# esp32_LoRa.net
KiCad netlist of a schematic drawn in EAGLE
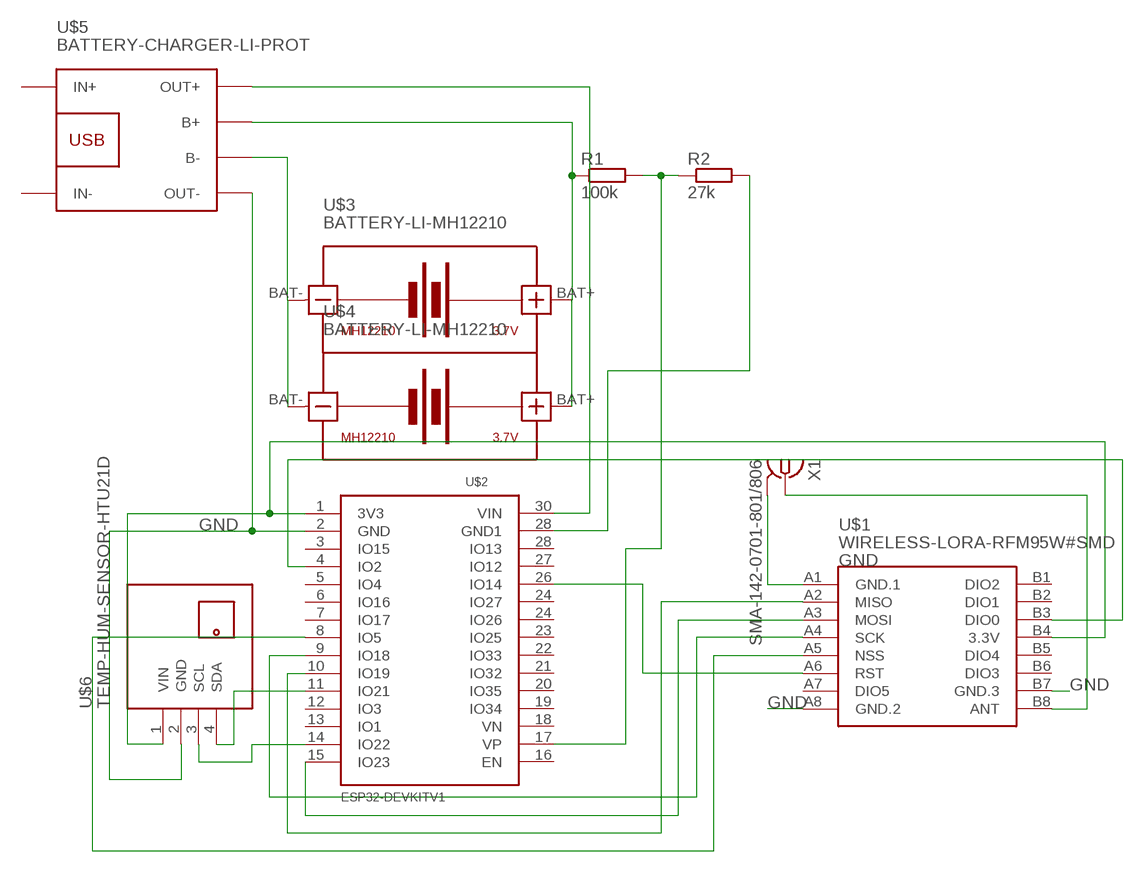
[diagram p0: schematic, sheet 1]

(export (version "E")
  (design (tool "Eeschema 10.0.6"))
  (components
    (comp (ref "R1")
      (value "100k")
      (footprint "eagle-import:0204_7")
      (libsource (lib "eagle-import") (part "R-EU_0204/7"))
    )
    (comp (ref "R2")
      (value "27k")
      (footprint "eagle-import:0204_7")
      (libsource (lib "eagle-import") (part "R-EU_0204/7"))
    )
    (comp (ref "U$1")
      (value "WIRELESS-LORA-RFM95W#SMD")
      (footprint "eagle-import:WIRELESS-LORA-RFM95W#SMD")
      (libsource (lib "eagle-import") (part "WIRELESS-LORA-RFM95W#SMD"))
    )
    (comp (ref "U$2")
      (value "ESP32DEVKITV1")
      (footprint "eagle-import:ESP32-DEVKITV1")
      (libsource (lib "eagle-import") (part "ESP32DEVKITV1"))
    )
    (comp (ref "U$3")
      (value "BATTERY-LI-MH12210")
      (footprint "eagle-import:BATTERY-LI-MH12210")
      (libsource (lib "eagle-import") (part "BATTERY-LI-MH12210"))
    )
    (comp (ref "U$4")
      (value "BATTERY-LI-MH12210")
      (footprint "eagle-import:BATTERY-LI-MH12210")
      (libsource (lib "eagle-import") (part "BATTERY-LI-MH12210"))
    )
    (comp (ref "U$5")
      (value "BATTERY-CHARGER-LI-PROT")
      (footprint "eagle-import:BATTERY-CHARGER-LI-PROT")
      (libsource (lib "eagle-import") (part "BATTERY-CHARGER-LI-PROT"))
    )
    (comp (ref "U$6")
      (value "TEMP-HUM-SENSOR-HTU21D")
      (footprint "eagle-import:TEMP-HUM-SENSOR-HTU21D")
      (libsource (lib "eagle-import") (part "TEMP-HUM-SENSOR-HTU21D"))
    )
    (comp (ref "X1")
      (value "SMA-142-0701-801/806")
      (footprint "eagle-import:J502-ND-142-0701-801_806")
      (fields (field (name "MF") "JOHNSON COMPONENTS") (field (name "MPN") "142-0701-801"))
      (libsource (lib "eagle-import") (part "SMA-142-0701-801/806"))
    )
  )
  (nets
    (net (code "1") (name "/GND") (class "Default")
      (node (ref "U$1") (pin "A1") (pinfunction "GND.1_A1") (pintype "power_in"))
      (node (ref "U$1") (pin "A8") (pinfunction "GND.2_A8") (pintype "power_in"))
      (node (ref "U$1") (pin "B7") (pinfunction "GND.3_B7") (pintype "power_in"))
      (node (ref "U$2") (pin "2") (pinfunction "GND_2") (pintype "bidirectional"))
      (node (ref "U$5") (pin "OUT-") (pinfunction "OUT-_OUT-") (pintype "bidirectional"))
      (node (ref "U$6") (pin "2") (pinfunction "GND_2") (pintype "power_in"))
      (node (ref "X1") (pin "G@1") (pinfunction "2_G@1") (pintype "passive"))
      (node (ref "X1") (pin "G@2") (pinfunction "2_G@2") (pintype "passive"))
      (node (ref "X1") (pin "G@3") (pinfunction "2_G@3") (pintype "passive"))
      (node (ref "X1") (pin "G@4") (pinfunction "2_G@4") (pintype "passive"))
    )
    (net (code "2") (name "Net-(R1-Pad1)") (class "Default")
      (node (ref "R1") (pin "1") (pinfunction "1_1") (pintype "passive"))
      (node (ref "U$3") (pin "BAT+") (pinfunction "BAT+_BAT+") (pintype "power_in"))
      (node (ref "U$4") (pin "BAT+") (pinfunction "BAT+_BAT+") (pintype "power_in"))
      (node (ref "U$5") (pin "B+") (pinfunction "B+_B+") (pintype "bidirectional"))
    )
    (net (code "3") (name "Net-(U$1-3.3V)") (class "Default")
      (node (ref "U$1") (pin "B4") (pinfunction "3.3V_B4") (pintype "power_in"))
      (node (ref "U$2") (pin "1") (pinfunction "3V3_1") (pintype "bidirectional"))
      (node (ref "U$6") (pin "1") (pinfunction "VIN_1") (pintype "power_in"))
    )
    (net (code "4") (name "Net-(U$1-ANT)") (class "Default")
      (node (ref "U$1") (pin "B8") (pinfunction "ANT_B8") (pintype "passive"))
      (node (ref "X1") (pin "1") (pinfunction "1_1") (pintype "passive"))
    )
    (net (code "5") (name "Net-(U$1-DIO0)") (class "Default")
      (node (ref "U$1") (pin "B3") (pinfunction "DIO0_B3") (pintype "bidirectional"))
      (node (ref "U$2") (pin "4") (pinfunction "IO2_4") (pintype "bidirectional"))
    )
    (net (code "6") (name "Net-(U$1-MISO)") (class "Default")
      (node (ref "U$1") (pin "A2") (pinfunction "MISO_A2") (pintype "bidirectional"))
      (node (ref "U$2") (pin "10") (pinfunction "IO19_10") (pintype "bidirectional"))
    )
    (net (code "7") (name "Net-(U$1-MOSI)") (class "Default")
      (node (ref "U$1") (pin "A3") (pinfunction "MOSI_A3") (pintype "bidirectional"))
      (node (ref "U$2") (pin "15") (pinfunction "IO23_15") (pintype "bidirectional"))
    )
    (net (code "8") (name "Net-(U$1-NSS)") (class "Default")
      (node (ref "U$1") (pin "A5") (pinfunction "NSS_A5") (pintype "bidirectional"))
      (node (ref "U$2") (pin "8") (pinfunction "IO5_8") (pintype "bidirectional"))
    )
    (net (code "9") (name "Net-(U$1-RST)") (class "Default")
      (node (ref "U$1") (pin "A6") (pinfunction "RST_A6") (pintype "bidirectional"))
      (node (ref "U$2") (pin "26") (pinfunction "IO14_26") (pintype "bidirectional"))
    )
    (net (code "10") (name "Net-(U$1-SCK)") (class "Default")
      (node (ref "U$1") (pin "A4") (pinfunction "SCK_A4") (pintype "bidirectional"))
      (node (ref "U$2") (pin "9") (pinfunction "IO18_9") (pintype "bidirectional"))
    )
    (net (code "11") (name "Net-(U$2-GND1)") (class "Default")
      (node (ref "R2") (pin "2") (pinfunction "2_2") (pintype "passive"))
      (node (ref "U$2") (pin "28") (pinfunction "GND1_28") (pintype "bidirectional"))
    )
    (net (code "12") (name "Net-(U$2-IO21)") (class "Default")
      (node (ref "U$2") (pin "11") (pinfunction "IO21_11") (pintype "bidirectional"))
      (node (ref "U$6") (pin "4") (pinfunction "SDA_4") (pintype "bidirectional"))
    )
    (net (code "13") (name "Net-(U$2-IO22)") (class "Default")
      (node (ref "U$2") (pin "14") (pinfunction "IO22_14") (pintype "bidirectional"))
      (node (ref "U$6") (pin "3") (pinfunction "SCL_3") (pintype "bidirectional"))
    )
    (net (code "14") (name "Net-(U$2-VIN)") (class "Default")
      (node (ref "U$2") (pin "30") (pinfunction "VIN_30") (pintype "bidirectional"))
      (node (ref "U$5") (pin "OUT+") (pinfunction "OUT+_OUT+") (pintype "bidirectional"))
    )
    (net (code "15") (name "Net-(U$2-VP)") (class "Default")
      (node (ref "R1") (pin "2") (pinfunction "2_2") (pintype "passive"))
      (node (ref "R2") (pin "1") (pinfunction "1_1") (pintype "passive"))
      (node (ref "U$2") (pin "17") (pinfunction "VP_17") (pintype "bidirectional"))
    )
    (net (code "16") (name "Net-(U$3-PadBAT-)") (class "Default")
      (node (ref "U$3") (pin "BAT-") (pinfunction "BAT-_BAT-") (pintype "power_in"))
      (node (ref "U$4") (pin "BAT-") (pinfunction "BAT-_BAT-") (pintype "power_in"))
      (node (ref "U$5") (pin "B-") (pinfunction "B-_B-") (pintype "bidirectional"))
    )
    (net (code "17") (name "unconnected-(U$1-DIO1-PadB2)") (class "Default")
      (node (ref "U$1") (pin "B2") (pinfunction "DIO1_B2") (pintype "bidirectional"))
    )
    (net (code "18") (name "unconnected-(U$1-DIO2-PadB1)") (class "Default")
      (node (ref "U$1") (pin "B1") (pinfunction "DIO2_B1") (pintype "bidirectional"))
    )
    (net (code "19") (name "unconnected-(U$1-DIO3-PadB6)") (class "Default")
      (node (ref "U$1") (pin "B6") (pinfunction "DIO3_B6") (pintype "bidirectional"))
    )
    (net (code "20") (name "unconnected-(U$1-DIO4-PadB5)") (class "Default")
      (node (ref "U$1") (pin "B5") (pinfunction "DIO4_B5") (pintype "bidirectional"))
    )
    (net (code "21") (name "unconnected-(U$1-DIO5-PadA7)") (class "Default")
      (node (ref "U$1") (pin "A7") (pinfunction "DIO5_A7") (pintype "bidirectional"))
    )
    (net (code "22") (name "unconnected-(U$2-EN-Pad16)") (class "Default")
      (node (ref "U$2") (pin "16") (pinfunction "EN_16") (pintype "bidirectional"))
    )
    (net (code "23") (name "unconnected-(U$2-IO1-Pad13)") (class "Default")
      (node (ref "U$2") (pin "13") (pinfunction "IO1_13") (pintype "bidirectional"))
    )
    (net (code "24") (name "unconnected-(U$2-IO3-Pad12)") (class "Default")
      (node (ref "U$2") (pin "12") (pinfunction "IO3_12") (pintype "bidirectional"))
    )
    (net (code "25") (name "unconnected-(U$2-IO4-Pad5)") (class "Default")
      (node (ref "U$2") (pin "5") (pinfunction "IO4_5") (pintype "bidirectional"))
    )
    (net (code "26") (name "unconnected-(U$2-IO12-Pad27)") (class "Default")
      (node (ref "U$2") (pin "27") (pinfunction "IO12_27") (pintype "bidirectional"))
    )
    (net (code "27") (name "unconnected-(U$2-IO13-Pad28)") (class "Default")
      (node (ref "U$2") (pin "28") (pinfunction "IO13_28") (pintype "bidirectional"))
    )
    (net (code "28") (name "unconnected-(U$2-IO15-Pad3)") (class "Default")
      (node (ref "U$2") (pin "3") (pinfunction "IO15_3") (pintype "bidirectional"))
    )
    (net (code "29") (name "unconnected-(U$2-IO16-Pad6)") (class "Default")
      (node (ref "U$2") (pin "6") (pinfunction "IO16_6") (pintype "bidirectional"))
    )
    (net (code "30") (name "unconnected-(U$2-IO17-Pad7)") (class "Default")
      (node (ref "U$2") (pin "7") (pinfunction "IO17_7") (pintype "bidirectional"))
    )
    (net (code "31") (name "unconnected-(U$2-IO25-Pad23)") (class "Default")
      (node (ref "U$2") (pin "23") (pinfunction "IO25_23") (pintype "bidirectional"))
    )
    (net (code "32") (name "unconnected-(U$2-IO26-Pad24)") (class "Default")
      (node (ref "U$2") (pin "24") (pinfunction "IO26_24") (pintype "bidirectional"))
    )
    (net (code "33") (name "unconnected-(U$2-IO27-Pad24)") (class "Default")
      (node (ref "U$2") (pin "24") (pinfunction "IO27_24") (pintype "bidirectional"))
    )
    (net (code "34") (name "unconnected-(U$2-IO32-Pad21)") (class "Default")
      (node (ref "U$2") (pin "21") (pinfunction "IO32_21") (pintype "bidirectional"))
    )
    (net (code "35") (name "unconnected-(U$2-IO33-Pad22)") (class "Default")
      (node (ref "U$2") (pin "22") (pinfunction "IO33_22") (pintype "bidirectional"))
    )
    (net (code "36") (name "unconnected-(U$2-IO34-Pad19)") (class "Default")
      (node (ref "U$2") (pin "19") (pinfunction "IO34_19") (pintype "bidirectional"))
    )
    (net (code "37") (name "unconnected-(U$2-IO35-Pad20)") (class "Default")
      (node (ref "U$2") (pin "20") (pinfunction "IO35_20") (pintype "bidirectional"))
    )
    (net (code "38") (name "unconnected-(U$2-VN-Pad18)") (class "Default")
      (node (ref "U$2") (pin "18") (pinfunction "VN_18") (pintype "bidirectional"))
    )
    (net (code "39") (name "unconnected-(U$5-PadIN+)") (class "Default")
      (node (ref "U$5") (pin "IN+") (pinfunction "IN+_IN+") (pintype "bidirectional"))
    )
    (net (code "40") (name "unconnected-(U$5-PadIN-)") (class "Default")
      (node (ref "U$5") (pin "IN-") (pinfunction "IN-_IN-") (pintype "bidirectional"))
    )
  )
)
